# board1.net
KiCad netlist of a schematic drawn in EAGLE
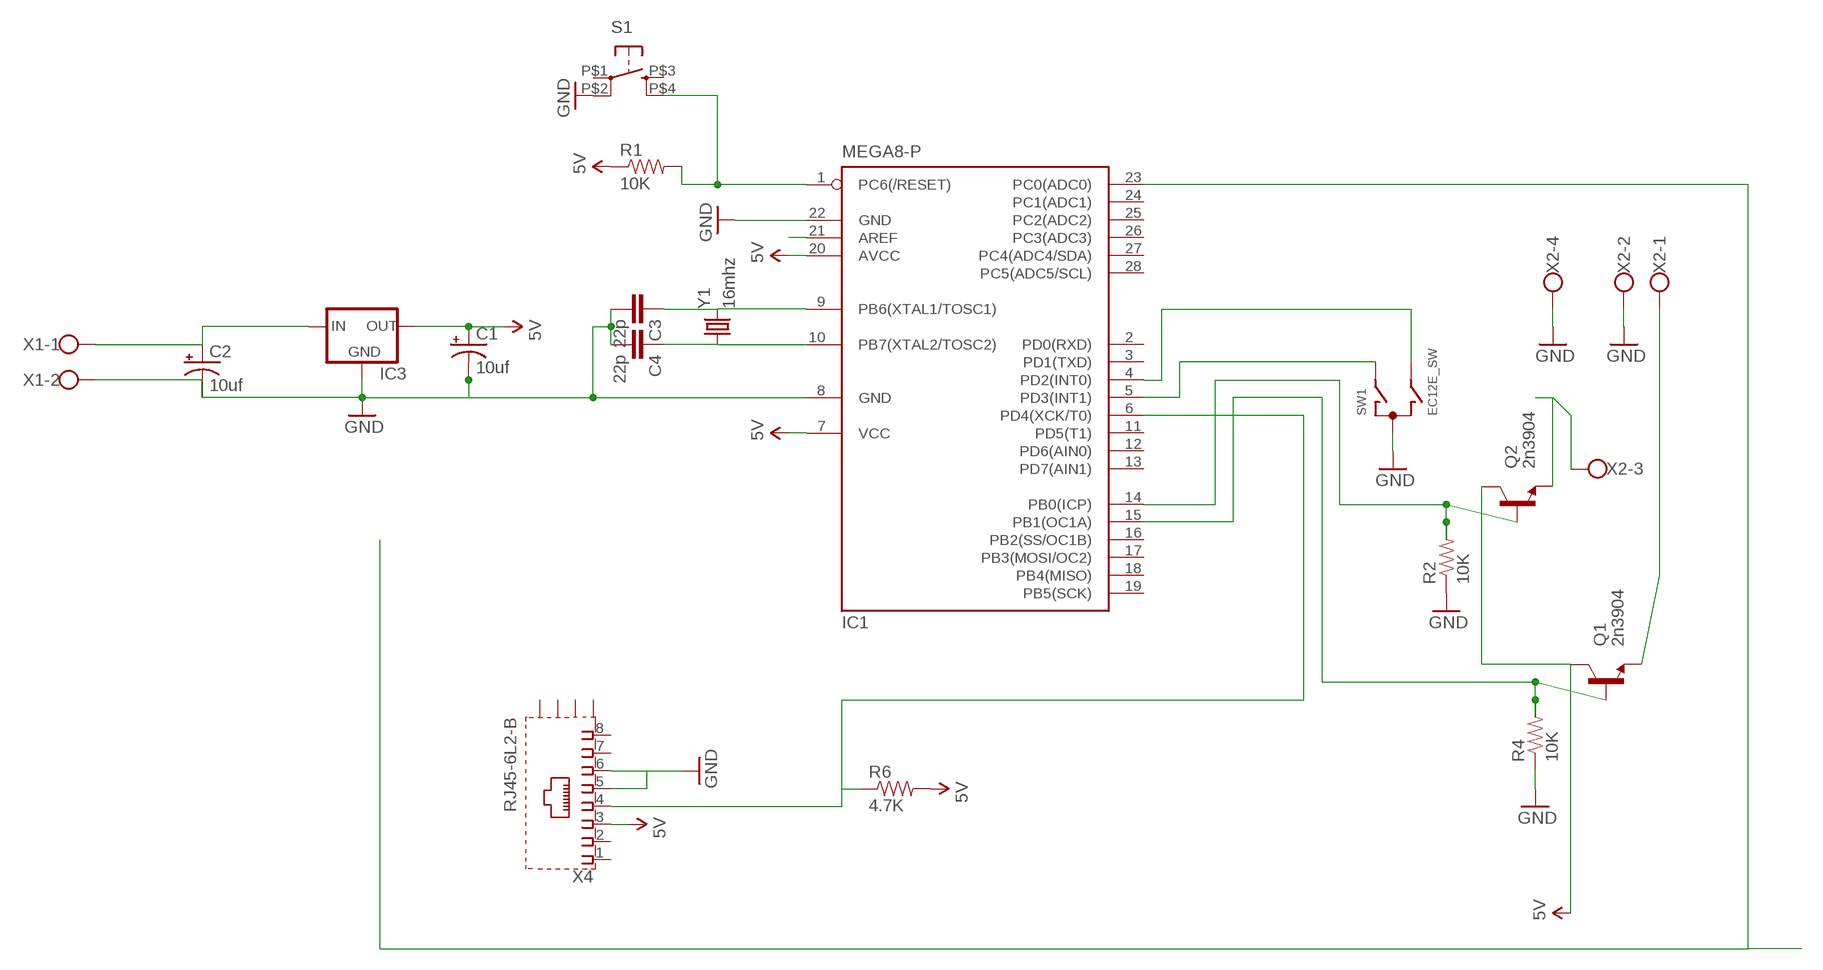
[diagram p0: schematic, sheet 1]

(export (version "E")
  (design (tool "Eeschema 10.0.6"))
  (components
    (comp (ref "C1")
      (value "10uf")
      (footprint "eagle-import:CPOL-RADIAL-10UF-25V")
      (libsource (lib "eagle-import") (part "CAP_POLPTH2"))
    )
    (comp (ref "C2")
      (value "10uf")
      (footprint "eagle-import:CPOL-RADIAL-10UF-25V")
      (libsource (lib "eagle-import") (part "CAP_POLPTH2"))
    )
    (comp (ref "C3")
      (value "22p")
      (footprint "eagle-import:AXIAL-5MM")
      (libsource (lib "eagle-import") (part "CAP_"))
    )
    (comp (ref "C4")
      (value "22p")
      (footprint "eagle-import:AXIAL-5MM")
      (libsource (lib "eagle-import") (part "CAP_"))
    )
    (comp (ref "IC1")
      (value "MEGA8-P")
      (footprint "eagle-import:DIL28-3")
      (libsource (lib "eagle-import") (part "MEGA8-P"))
    )
    (comp (ref "IC3")
      (value "V_REG_78XXSINK")
      (footprint "eagle-import:TO220-IGO")
      (libsource (lib "eagle-import") (part "V_REG_78XXSINK"))
    )
    (comp (ref "Q1")
      (value "2n3904")
      (footprint "eagle-import:TO-92-AMMO")
      (libsource (lib "eagle-import") (part "TRANSISTOR_NPNTO-92-AMMO"))
    )
    (comp (ref "Q2")
      (value "2n3904")
      (footprint "eagle-import:TO-92-AMMO")
      (libsource (lib "eagle-import") (part "TRANSISTOR_NPNTO-92-AMMO"))
    )
    (comp (ref "R1")
      (value "10K")
      (footprint "eagle-import:AXIAL-0.3")
      (libsource (lib "eagle-import") (part "RESISTORAXIAL-0.3"))
    )
    (comp (ref "R2")
      (value "10K")
      (footprint "eagle-import:AXIAL-0.3")
      (libsource (lib "eagle-import") (part "RESISTORAXIAL-0.3"))
    )
    (comp (ref "R4")
      (value "10K")
      (footprint "eagle-import:AXIAL-0.3")
      (libsource (lib "eagle-import") (part "RESISTORAXIAL-0.3"))
    )
    (comp (ref "R6")
      (value "4.7K")
      (footprint "eagle-import:AXIAL-0.3-KIT")
      (libsource (lib "eagle-import") (part "RESISTORKIT"))
    )
    (comp (ref "S1")
      (value "TAC_SWITCHKSA_SEALED")
      (footprint "eagle-import:KSA_SEALED_TAC_SWITCH")
      (libsource (lib "eagle-import") (part "TAC_SWITCHKSA_SEALED"))
    )
    (comp (ref "SW1")
      (value "EC12E_SW")
      (footprint "eagle-import:ALPS_EC12E_SW")
      (fields (field (name "MPN") "EC12E2424407"))
      (libsource (lib "eagle-import") (part "EC12E_SW"))
    )
    (comp (ref "X1")
      (value "W237-102")
      (footprint "eagle-import:W237-102")
      (fields (field (name "MPN") "237-102"))
      (libsource (lib "eagle-import") (part "W237-102"))
    )
    (comp (ref "X2")
      (value "W237-4")
      (footprint "eagle-import:W237-4")
      (libsource (lib "eagle-import") (part "W237-4"))
    )
    (comp (ref "X4")
      (value "RJ45-6L2-B")
      (footprint "eagle-import:RJ45-SHIELD2")
      (libsource (lib "eagle-import") (part "RJ452-B-6L"))
    )
    (comp (ref "Y1")
      (value "16mhz")
      (footprint "eagle-import:HC49US")
      (libsource (lib "eagle-import") (part "CRYSTALHC49US"))
    )
  )
  (nets
    (net (code "1") (name "5V") (class "Default")
      (node (ref "C1") (pin "1") (pinfunction "+_1") (pintype "passive"))
      (node (ref "IC1") (pin "20") (pinfunction "AVCC_20") (pintype "power_in"))
      (node (ref "IC1") (pin "7") (pinfunction "VCC_7") (pintype "power_in"))
      (node (ref "IC3") (pin "OUT") (pinfunction "OUT_OUT") (pintype "output"))
      (node (ref "Q1") (pin "3") (pinfunction "C_3") (pintype "passive"))
      (node (ref "Q2") (pin "3") (pinfunction "C_3") (pintype "passive"))
      (node (ref "R1") (pin "P$1") (pinfunction "1_P$1") (pintype "passive"))
      (node (ref "R6") (pin "P$2") (pinfunction "2_P$2") (pintype "passive"))
      (node (ref "X4") (pin "3") (pinfunction "3_3") (pintype "passive"))
    )
    (net (code "2") (name "GND") (class "Default")
      (node (ref "C1") (pin "2") (pinfunction "-_2") (pintype "passive"))
      (node (ref "C2") (pin "2") (pinfunction "-_2") (pintype "passive"))
      (node (ref "C3") (pin "P$2") (pinfunction "2_P$2") (pintype "passive"))
      (node (ref "C4") (pin "P$2") (pinfunction "2_P$2") (pintype "passive"))
      (node (ref "IC1") (pin "22") (pinfunction "GND_22") (pintype "power_in"))
      (node (ref "IC1") (pin "8") (pinfunction "GND_8") (pintype "power_in"))
      (node (ref "IC3") (pin "GND") (pinfunction "GND_GND") (pintype "input"))
      (node (ref "R2") (pin "P$1") (pinfunction "1_P$1") (pintype "passive"))
      (node (ref "R4") (pin "P$1") (pinfunction "1_P$1") (pintype "passive"))
      (node (ref "S1") (pin "P$2") (pinfunction "2_P$2") (pintype "passive"))
      (node (ref "SW1") (pin "C") (pinfunction "C_C") (pintype "passive"))
      (node (ref "X1") (pin "2") (pinfunction "KL_2") (pintype "passive"))
      (node (ref "X2") (pin "2") (pinfunction "KL_2") (pintype "passive"))
      (node (ref "X2") (pin "4") (pinfunction "KL_4") (pintype "passive"))
      (node (ref "X4") (pin "5") (pinfunction "5_5") (pintype "passive"))
      (node (ref "X4") (pin "6") (pinfunction "6_6") (pintype "passive"))
    )
    (net (code "3") (name "Net-(C2-+)") (class "Default")
      (node (ref "C2") (pin "1") (pinfunction "+_1") (pintype "passive"))
      (node (ref "IC3") (pin "IN") (pinfunction "IN_IN") (pintype "input"))
      (node (ref "X1") (pin "1") (pinfunction "KL_1") (pintype "passive"))
    )
    (net (code "4") (name "Net-(C3-1)") (class "Default")
      (node (ref "C3") (pin "P$1") (pinfunction "1_P$1") (pintype "passive"))
      (node (ref "IC1") (pin "9") (pinfunction "PB6(XTAL1/TOSC1)_9") (pintype "bidirectional"))
      (node (ref "Y1") (pin "2") (pinfunction "2_2") (pintype "passive"))
    )
    (net (code "5") (name "Net-(C4-1)") (class "Default")
      (node (ref "C4") (pin "P$1") (pinfunction "1_P$1") (pintype "passive"))
      (node (ref "IC1") (pin "10") (pinfunction "PB7(XTAL2/TOSC2)_10") (pintype "bidirectional"))
      (node (ref "Y1") (pin "1") (pinfunction "1_1") (pintype "passive"))
    )
    (net (code "6") (name "Net-(IC1-PB0(ICP))") (class "Default")
      (node (ref "IC1") (pin "14") (pinfunction "PB0(ICP)_14") (pintype "bidirectional"))
      (node (ref "Q2") (pin "2") (pinfunction "B_2") (pintype "passive"))
      (node (ref "R2") (pin "P$2") (pinfunction "2_P$2") (pintype "passive"))
    )
    (net (code "7") (name "Net-(IC1-PB1(OC1A))") (class "Default")
      (node (ref "IC1") (pin "15") (pinfunction "PB1(OC1A)_15") (pintype "bidirectional"))
      (node (ref "Q1") (pin "2") (pinfunction "B_2") (pintype "passive"))
      (node (ref "R4") (pin "P$2") (pinfunction "2_P$2") (pintype "passive"))
    )
    (net (code "8") (name "Net-(IC1-PC6({slash}RESET))") (class "Default")
      (node (ref "IC1") (pin "1") (pinfunction "PC6(/RESET)_1") (pintype "bidirectional"))
      (node (ref "R1") (pin "P$2") (pinfunction "2_P$2") (pintype "passive"))
      (node (ref "S1") (pin "P$4") (pinfunction "4_P$4") (pintype "passive"))
    )
    (net (code "9") (name "Net-(IC1-PD2(INT0))") (class "Default")
      (node (ref "IC1") (pin "4") (pinfunction "PD2(INT0)_4") (pintype "bidirectional"))
      (node (ref "SW1") (pin "B") (pinfunction "B_B") (pintype "passive"))
    )
    (net (code "10") (name "Net-(IC1-PD3(INT1))") (class "Default")
      (node (ref "IC1") (pin "5") (pinfunction "PD3(INT1)_5") (pintype "bidirectional"))
      (node (ref "SW1") (pin "A") (pinfunction "A_A") (pintype "passive"))
    )
    (net (code "11") (name "Net-(IC1-PD4(XCK{slash}T0))") (class "Default")
      (node (ref "IC1") (pin "6") (pinfunction "PD4(XCK/T0)_6") (pintype "bidirectional"))
      (node (ref "R6") (pin "P$1") (pinfunction "1_P$1") (pintype "passive"))
      (node (ref "X4") (pin "4") (pinfunction "4_4") (pintype "passive"))
    )
    (net (code "12") (name "Net-(Q1-E)") (class "Default")
      (node (ref "Q1") (pin "1") (pinfunction "E_1") (pintype "passive"))
      (node (ref "X2") (pin "1") (pinfunction "KL_1") (pintype "passive"))
    )
    (net (code "13") (name "Net-(Q2-E)") (class "Default")
      (node (ref "Q2") (pin "1") (pinfunction "E_1") (pintype "passive"))
      (node (ref "X2") (pin "3") (pinfunction "KL_3") (pintype "passive"))
    )
    (net (code "14") (name "unconnected-(IC1-AREF-Pad21)") (class "Default")
      (node (ref "IC1") (pin "21") (pinfunction "AREF_21") (pintype "passive"))
    )
    (net (code "15") (name "unconnected-(IC1-PB2(SS{slash}OC1B)-Pad16)") (class "Default")
      (node (ref "IC1") (pin "16") (pinfunction "PB2(SS/OC1B)_16") (pintype "bidirectional"))
    )
    (net (code "16") (name "unconnected-(IC1-PB3(MOSI{slash}OC2)-Pad17)") (class "Default")
      (node (ref "IC1") (pin "17") (pinfunction "PB3(MOSI/OC2)_17") (pintype "bidirectional"))
    )
    (net (code "17") (name "unconnected-(IC1-PB4(MISO)-Pad18)") (class "Default")
      (node (ref "IC1") (pin "18") (pinfunction "PB4(MISO)_18") (pintype "bidirectional"))
    )
    (net (code "18") (name "unconnected-(IC1-PB5(SCK)-Pad19)") (class "Default")
      (node (ref "IC1") (pin "19") (pinfunction "PB5(SCK)_19") (pintype "bidirectional"))
    )
    (net (code "19") (name "unconnected-(IC1-PC0(ADC0)-Pad23)") (class "Default")
      (node (ref "IC1") (pin "23") (pinfunction "PC0(ADC0)_23") (pintype "bidirectional"))
    )
    (net (code "20") (name "unconnected-(IC1-PC1(ADC1)-Pad24)") (class "Default")
      (node (ref "IC1") (pin "24") (pinfunction "PC1(ADC1)_24") (pintype "bidirectional"))
    )
    (net (code "21") (name "unconnected-(IC1-PC2(ADC2)-Pad25)") (class "Default")
      (node (ref "IC1") (pin "25") (pinfunction "PC2(ADC2)_25") (pintype "bidirectional"))
    )
    (net (code "22") (name "unconnected-(IC1-PC3(ADC3)-Pad26)") (class "Default")
      (node (ref "IC1") (pin "26") (pinfunction "PC3(ADC3)_26") (pintype "bidirectional"))
    )
    (net (code "23") (name "unconnected-(IC1-PC4(ADC4{slash}SDA)-Pad27)") (class "Default")
      (node (ref "IC1") (pin "27") (pinfunction "PC4(ADC4/SDA)_27") (pintype "bidirectional"))
    )
    (net (code "24") (name "unconnected-(IC1-PC5(ADC5{slash}SCL)-Pad28)") (class "Default")
      (node (ref "IC1") (pin "28") (pinfunction "PC5(ADC5/SCL)_28") (pintype "bidirectional"))
    )
    (net (code "25") (name "unconnected-(IC1-PD0(RXD)-Pad2)") (class "Default")
      (node (ref "IC1") (pin "2") (pinfunction "PD0(RXD)_2") (pintype "bidirectional"))
    )
    (net (code "26") (name "unconnected-(IC1-PD1(TXD)-Pad3)") (class "Default")
      (node (ref "IC1") (pin "3") (pinfunction "PD1(TXD)_3") (pintype "bidirectional"))
    )
    (net (code "27") (name "unconnected-(IC1-PD5(T1)-Pad11)") (class "Default")
      (node (ref "IC1") (pin "11") (pinfunction "PD5(T1)_11") (pintype "bidirectional"))
    )
    (net (code "28") (name "unconnected-(IC1-PD6(AIN0)-Pad12)") (class "Default")
      (node (ref "IC1") (pin "12") (pinfunction "PD6(AIN0)_12") (pintype "bidirectional"))
    )
    (net (code "29") (name "unconnected-(IC1-PD7(AIN1)-Pad13)") (class "Default")
      (node (ref "IC1") (pin "13") (pinfunction "PD7(AIN1)_13") (pintype "bidirectional"))
    )
    (net (code "30") (name "unconnected-(S1-1-PadP$1)") (class "Default")
      (node (ref "S1") (pin "P$1") (pinfunction "1_P$1") (pintype "passive"))
    )
    (net (code "31") (name "unconnected-(S1-3-PadP$3)") (class "Default")
      (node (ref "S1") (pin "P$3") (pinfunction "3_P$3") (pintype "passive"))
    )
    (net (code "32") (name "unconnected-(X4-Pad1)") (class "Default")
      (node (ref "X4") (pin "1") (pinfunction "1_1") (pintype "passive"))
    )
    (net (code "33") (name "unconnected-(X4-Pad2)") (class "Default")
      (node (ref "X4") (pin "2") (pinfunction "2_2") (pintype "passive"))
    )
    (net (code "34") (name "unconnected-(X4-Pad7)") (class "Default")
      (node (ref "X4") (pin "7") (pinfunction "7_7") (pintype "passive"))
    )
    (net (code "35") (name "unconnected-(X4-Pad8)") (class "Default")
      (node (ref "X4") (pin "8") (pinfunction "8_8") (pintype "passive"))
    )
    (net (code "36") (name "unconnected-(X4-S-PadS1)") (class "Default")
      (node (ref "X4") (pin "S1") (pinfunction "S_S1") (pintype "passive"))
    )
    (net (code "37") (name "unconnected-(X4-S-PadS2)") (class "Default")
      (node (ref "X4") (pin "S2") (pinfunction "S_S2") (pintype "passive"))
    )
    (net (code "38") (name "unconnected-(X4-S-PadS3)") (class "Default")
      (node (ref "X4") (pin "S3") (pinfunction "S_S3") (pintype "passive"))
    )
    (net (code "39") (name "unconnected-(X4-S-PadS4)") (class "Default")
      (node (ref "X4") (pin "S4") (pinfunction "S_S4") (pintype "passive"))
    )
  )
)
